# SD_USB_FMU_REV_1B.net
KiCad netlist of a schematic drawn in Altium Designer
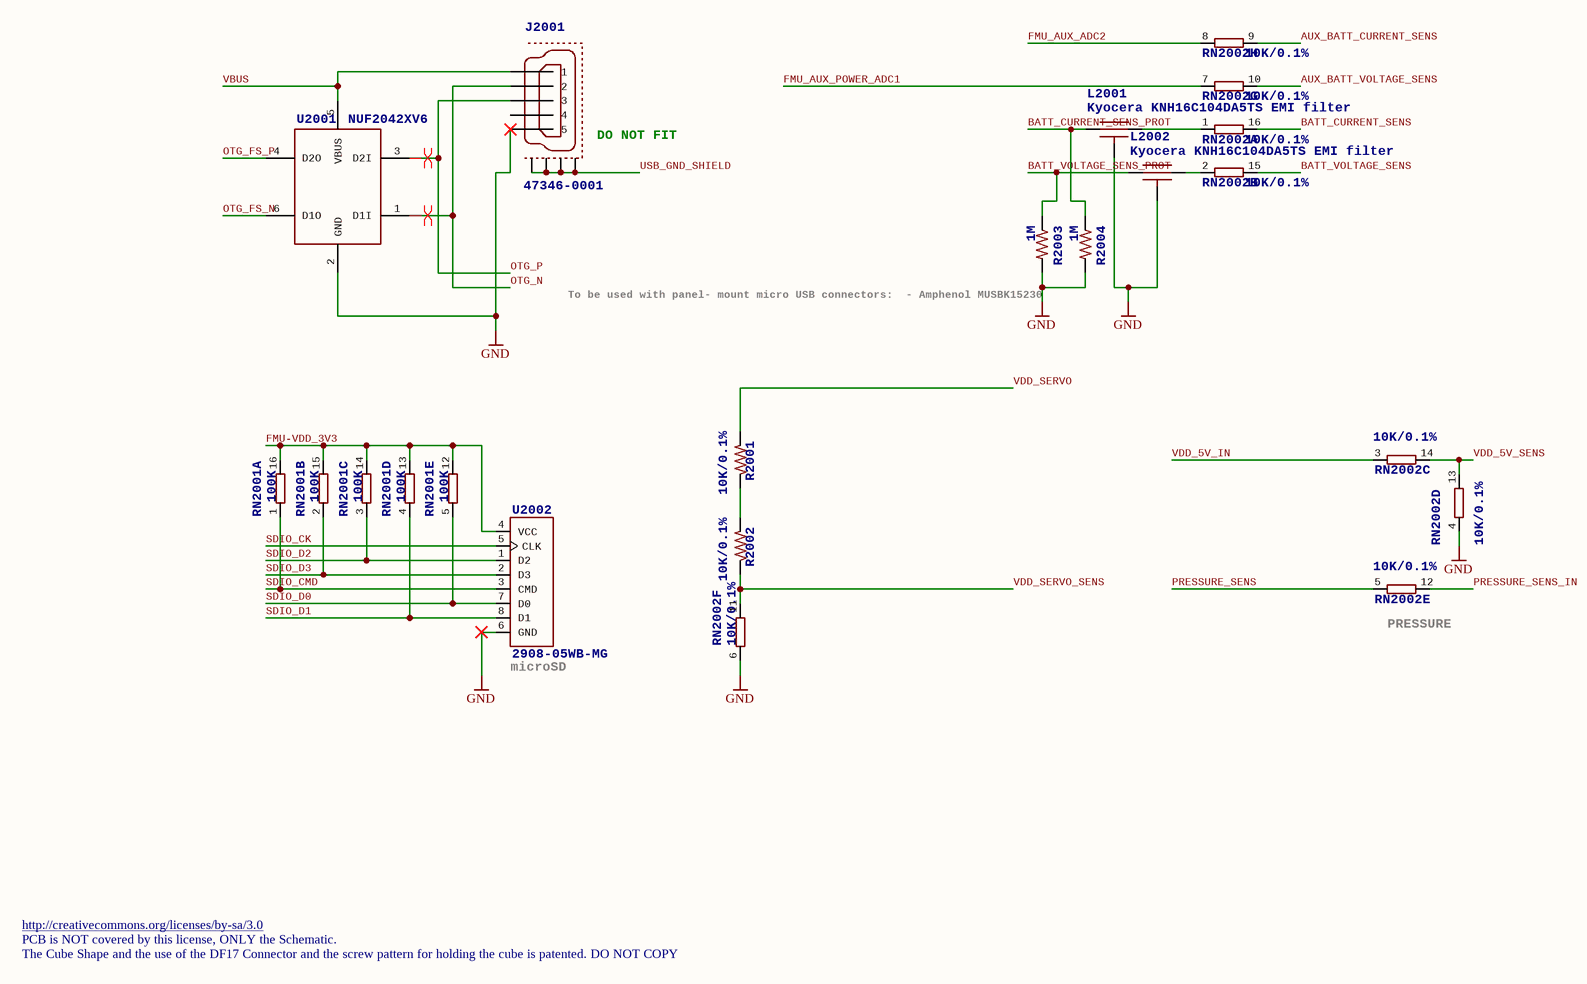
[diagram p0: SD_USB_FMU_REV_1B.SchDoc]

(export (version "E")
  (design (tool "Eeschema 10.0.6"))
  (components
    (comp (ref "J2001")
      (value "47346-0001")
      (footprint "MOLEX-47346-0001")
      (description "MICRO USB B, BOTTOM MOUNT")
      (libsource (lib "pixhawk2") (part "MOLEX-47346-0001"))
    )
    (comp (ref "L2001")
      (value "Kyocera KNH16C104DA5TS EMI filter")
      (footprint "KYOCERA-KNH16-DA")
      (description "FILTER CAP 0.1UF 2A 25V 0603")
      (libsource (lib "pixhawk2") (part "KNH16C104DA5TS"))
    )
    (comp (ref "L2002")
      (value "Kyocera KNH16C104DA5TS EMI filter")
      (footprint "KYOCERA-KNH16-DA")
      (description "FILTER CAP 0.1UF 2A 25V 0603")
      (libsource (lib "pixhawk2") (part "KNH16C104DA5TS"))
    )
    (comp (ref "R2001")
      (value "10K/0.1%")
      (footprint "0402-RES")
      (description "RES 10K OHM 1/16W .1% 0402 SMD")
      (libsource (lib "pixhawk2") (part "RESISTOR0402-RES"))
    )
    (comp (ref "R2002")
      (value "10K/0.1%")
      (footprint "0402-RES")
      (description "RES 10K OHM 1/16W .1% 0402 SMD")
      (libsource (lib "pixhawk2") (part "RESISTOR0402-RES"))
    )
    (comp (ref "R2003")
      (value "1M")
      (footprint "0402-RES")
      (description "RES 1M OHM 1/16W 1% 0402 SMD")
      (libsource (lib "pixhawk2") (part "RESISTOR0402-RES"))
    )
    (comp (ref "R2004")
      (value "1M")
      (footprint "0402-RES")
      (description "RES 1M OHM 1/16W 1% 0402 SMD")
      (libsource (lib "pixhawk2") (part "RESISTOR0402-RES"))
    )
    (comp (ref "RN2001")
      (value "100K")
      (footprint "EXB2HV")
      (description "RES ARRAY 100K OHM 8 RES 1506")
      (libsource (lib "pixhawk2") (part "8R-NEXB2HV-100K"))
    )
    (comp (ref "RN2002")
      (value "10K/0.1%")
      (footprint "EXB2HV")
      (description "RES ARRAY 10K OHM 8 RES 1506")
      (libsource (lib "pixhawk2") (part "8R-NEXB2HV-10K"))
    )
    (comp (ref "U2001")
      (value "NUF2042XV6")
      (footprint "SOT563-6")
      (description "IC FILTER USB ESD PROTECT SOT363")
      (libsource (lib "pixhawk2") (part "NUF2042XV6"))
    )
    (comp (ref "U2002")
      (value "2908-05WB-MG")
      (footprint "MICROSD")
      (description "CONN MICRO SD CARD PUSH-PUSH R/A")
      (libsource (lib "baseboard") (part "MICROSDSDI"))
    )
  )
  (nets
    (net (code "1") (name "/AUX_BATT_CURRENT_SENS") (class "Default")
      (node (ref "RN2002") (pin "9") (pinfunction "2_9") (pintype "passive"))
    )
    (net (code "2") (name "/AUX_BATT_VOLTAGE_SENS") (class "Default")
      (node (ref "RN2002") (pin "10") (pinfunction "2_10") (pintype "passive"))
    )
    (net (code "3") (name "/BATT_CURRENT_SENS") (class "Default")
      (node (ref "RN2002") (pin "16") (pinfunction "2_16") (pintype "passive"))
    )
    (net (code "4") (name "/BATT_CURRENT_SENS_PROT") (class "Default")
      (node (ref "L2001") (pin "P$1") (pinfunction "P$1_P$1") (pintype "passive"))
      (node (ref "R2004") (pin "P$1") (pinfunction "1_P$1") (pintype "passive"))
    )
    (net (code "5") (name "/BATT_VOLTAGE_SENS") (class "Default")
      (node (ref "RN2002") (pin "15") (pinfunction "2_15") (pintype "passive"))
    )
    (net (code "6") (name "/BATT_VOLTAGE_SENS_PROT") (class "Default")
      (node (ref "L2002") (pin "P$1") (pinfunction "P$1_P$1") (pintype "passive"))
      (node (ref "R2003") (pin "P$1") (pinfunction "1_P$1") (pintype "passive"))
    )
    (net (code "7") (name "/FMU-VDD_3V3") (class "Default")
      (node (ref "RN2001") (pin "12") (pinfunction "2_12") (pintype "passive"))
      (node (ref "RN2001") (pin "13") (pinfunction "2_13") (pintype "passive"))
      (node (ref "RN2001") (pin "14") (pinfunction "2_14") (pintype "passive"))
      (node (ref "RN2001") (pin "15") (pinfunction "2_15") (pintype "passive"))
      (node (ref "RN2001") (pin "16") (pinfunction "2_16") (pintype "passive"))
      (node (ref "U2002") (pin "4") (pinfunction "VCC_4") (pintype "passive"))
    )
    (net (code "8") (name "/FMU_AUX_ADC2") (class "Default")
      (node (ref "RN2002") (pin "8") (pinfunction "1_8") (pintype "passive"))
    )
    (net (code "9") (name "/FMU_AUX_POWER_ADC1") (class "Default")
      (node (ref "RN2002") (pin "7") (pinfunction "1_7") (pintype "passive"))
    )
    (net (code "10") (name "/OTG_FS_N") (class "Default")
      (node (ref "U2001") (pin "6") (pinfunction "D1O_6") (pintype "passive"))
    )
    (net (code "11") (name "/OTG_FS_P") (class "Default")
      (node (ref "U2001") (pin "4") (pinfunction "D2O_4") (pintype "passive"))
    )
    (net (code "12") (name "/OTG_N") (class "Default")
      (node (ref "J2001") (pin "D-") (pinfunction "2_D-") (pintype "passive"))
      (node (ref "U2001") (pin "1") (pinfunction "D1I_1") (pintype "passive"))
    )
    (net (code "13") (name "/OTG_P") (class "Default")
      (node (ref "J2001") (pin "D+") (pinfunction "3_D+") (pintype "passive"))
      (node (ref "U2001") (pin "3") (pinfunction "D2I_3") (pintype "passive"))
    )
    (net (code "14") (name "/PRESSURE_SENS") (class "Default")
      (node (ref "RN2002") (pin "5") (pinfunction "1_5") (pintype "passive"))
    )
    (net (code "15") (name "/PRESSURE_SENS_IN") (class "Default")
      (node (ref "RN2002") (pin "12") (pinfunction "2_12") (pintype "passive"))
    )
    (net (code "16") (name "/SDIO_CK") (class "Default")
      (node (ref "U2002") (pin "5") (pinfunction "CLK_5") (pintype "passive"))
    )
    (net (code "17") (name "/SDIO_CMD") (class "Default")
      (node (ref "RN2001") (pin "1") (pinfunction "1_1") (pintype "passive"))
      (node (ref "U2002") (pin "3") (pinfunction "CMD_3") (pintype "passive"))
    )
    (net (code "18") (name "/SDIO_D0") (class "Default")
      (node (ref "RN2001") (pin "5") (pinfunction "1_5") (pintype "passive"))
      (node (ref "U2002") (pin "7") (pinfunction "D0_7") (pintype "passive"))
    )
    (net (code "19") (name "/SDIO_D1") (class "Default")
      (node (ref "RN2001") (pin "4") (pinfunction "1_4") (pintype "passive"))
      (node (ref "U2002") (pin "8") (pinfunction "D1_8") (pintype "passive"))
    )
    (net (code "20") (name "/SDIO_D2") (class "Default")
      (node (ref "RN2001") (pin "3") (pinfunction "1_3") (pintype "passive"))
      (node (ref "U2002") (pin "1") (pinfunction "D2_1") (pintype "passive"))
    )
    (net (code "21") (name "/SDIO_D3") (class "Default")
      (node (ref "RN2001") (pin "2") (pinfunction "1_2") (pintype "passive"))
      (node (ref "U2002") (pin "2") (pinfunction "D3_2") (pintype "passive"))
    )
    (net (code "22") (name "/USB_GND_SHIELD") (class "Default")
      (node (ref "J2001") (pin "GND1") (pinfunction "GND1_GND1") (pintype "passive"))
      (node (ref "J2001") (pin "GND2") (pinfunction "GND2_GND2") (pintype "passive"))
      (node (ref "J2001") (pin "GND3") (pinfunction "GND3_GND3") (pintype "passive"))
      (node (ref "J2001") (pin "GND4") (pinfunction "GND4_GND4") (pintype "passive"))
    )
    (net (code "23") (name "/VBUS") (class "Default")
      (node (ref "J2001") (pin "VBUS") (pinfunction "1_VBUS") (pintype "open_emitter"))
      (node (ref "U2001") (pin "5") (pinfunction "VBUS_5") (pintype "passive"))
    )
    (net (code "24") (name "/VDD_5V_IN") (class "Default")
      (node (ref "RN2002") (pin "3") (pinfunction "1_3") (pintype "passive"))
    )
    (net (code "25") (name "/VDD_5V_SENS") (class "Default")
      (node (ref "RN2002") (pin "13") (pinfunction "2_13") (pintype "passive"))
      (node (ref "RN2002") (pin "14") (pinfunction "2_14") (pintype "passive"))
    )
    (net (code "26") (name "/VDD_SERVO") (class "Default")
      (node (ref "R2001") (pin "P$2") (pinfunction "2_P$2") (pintype "passive"))
    )
    (net (code "27") (name "/VDD_SERVO_SENS") (class "Default")
      (node (ref "R2002") (pin "P$1") (pinfunction "1_P$1") (pintype "passive"))
      (node (ref "RN2002") (pin "11") (pinfunction "2_11") (pintype "passive"))
    )
    (net (code "28") (name "GND") (class "Default")
      (node (ref "J2001") (pin "GND") (pinfunction "5_GND") (pintype "open_emitter"))
      (node (ref "L2001") (pin "GND") (pinfunction "GND_GND") (pintype "passive"))
      (node (ref "L2002") (pin "GND") (pinfunction "GND_GND") (pintype "passive"))
      (node (ref "R2003") (pin "P$2") (pinfunction "2_P$2") (pintype "passive"))
      (node (ref "R2004") (pin "P$2") (pinfunction "2_P$2") (pintype "passive"))
      (node (ref "RN2002") (pin "4") (pinfunction "1_4") (pintype "passive"))
      (node (ref "RN2002") (pin "6") (pinfunction "1_6") (pintype "passive"))
      (node (ref "U2001") (pin "2") (pinfunction "GND_2") (pintype "passive"))
      (node (ref "U2002") (pin "6") (pinfunction "GND_6") (pintype "open_emitter"))
    )
    (net (code "29") (name "Net-(L2001-PadP$2)") (class "Default")
      (node (ref "L2001") (pin "P$2") (pinfunction "P$2_P$2") (pintype "passive"))
      (node (ref "RN2002") (pin "1") (pinfunction "1_1") (pintype "passive"))
    )
    (net (code "30") (name "Net-(R2001-1)") (class "Default")
      (node (ref "R2001") (pin "P$1") (pinfunction "1_P$1") (pintype "passive"))
      (node (ref "R2002") (pin "P$2") (pinfunction "2_P$2") (pintype "passive"))
    )
    (net (code "31") (name "Net-(RN2002B-1)") (class "Default")
      (node (ref "L2002") (pin "P$2") (pinfunction "P$2_P$2") (pintype "passive"))
      (node (ref "RN2002") (pin "2") (pinfunction "1_2") (pintype "passive"))
    )
    (net (code "32") (name "unconnected-(J2001-4-PadID)") (class "Default")
      (node (ref "J2001") (pin "ID") (pinfunction "4_ID") (pintype "passive"))
    )
  )
)
